# Relays.net
KiCad netlist of a schematic drawn in Altium Designer
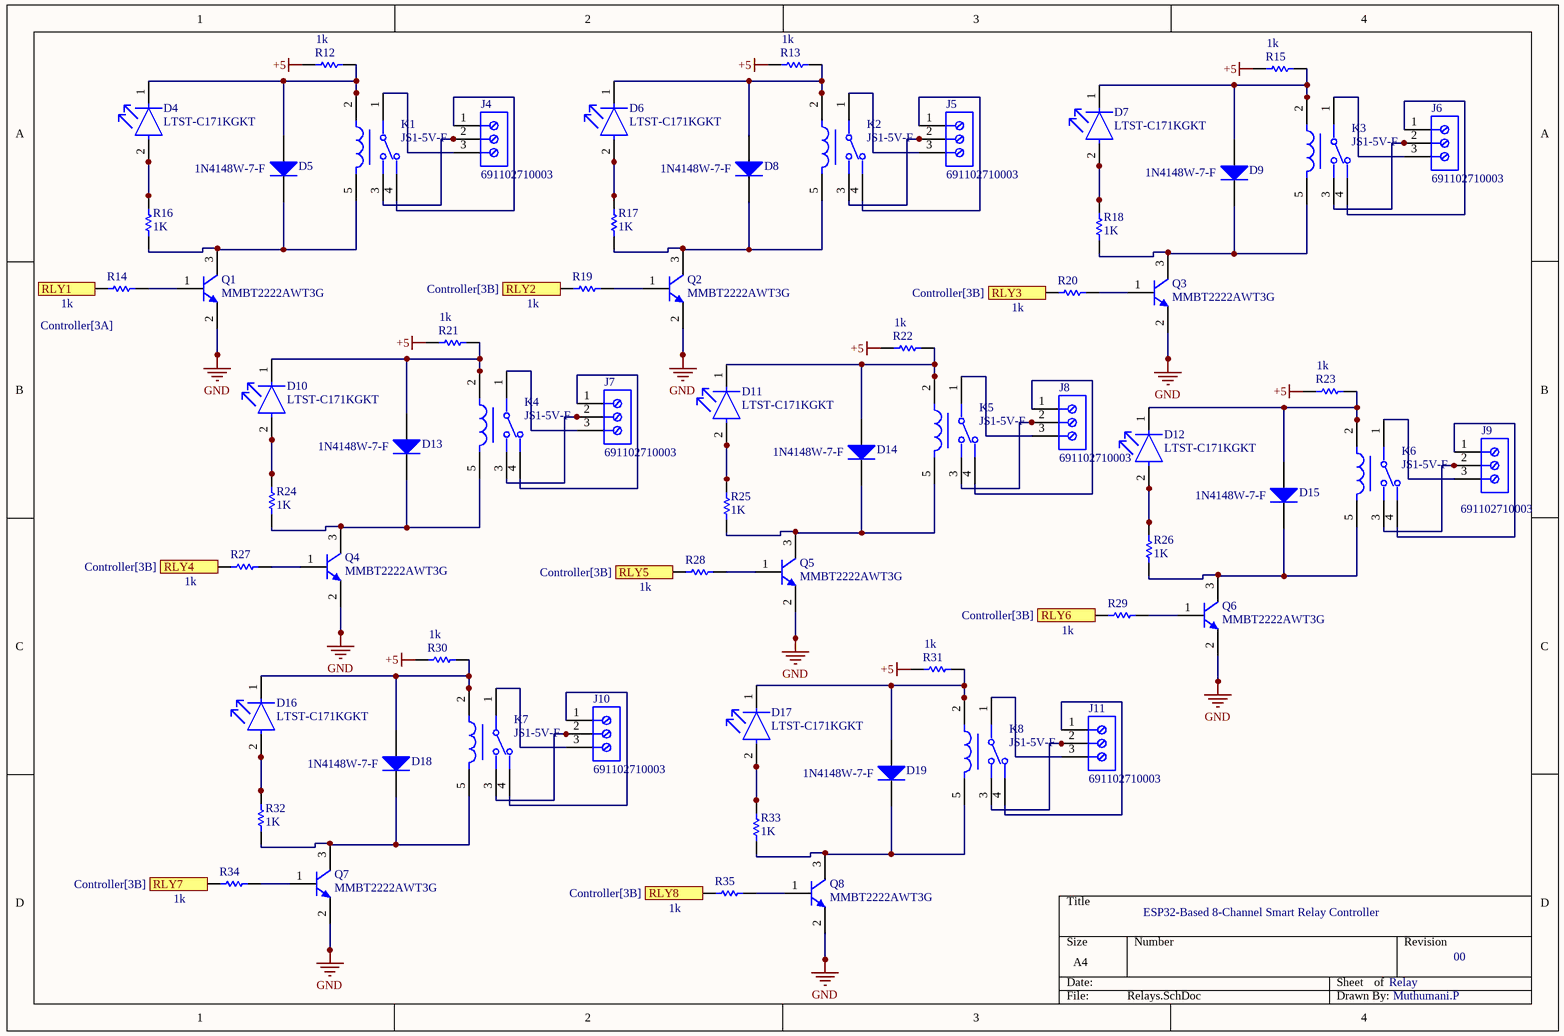
[diagram p0: Relays.SchDoc]

(export (version "E")
  (design (tool "Eeschema 10.0.6"))
  (components
    (comp (ref "D4")
      (value "LTST-C171KGKT")
      (footprint "FP-LTST-C171KGKT-MFG")
      (description "LED GREEN CLEAR SMD")
      (libsource (lib "Altium Content Vault") (part "8706943c75ba83719d021d2fdc84c58"))
    )
    (comp (ref "D5")
      (value "1N4148W-7-F")
      (footprint "DIOD-SOD123-2_V")
      (description "Fast Switching Diode, 100 V, 0.15 A, -65 to 150 degC, 2-Pin?SOD123, RoHS, Tape and Reel")
      (fields (field (name "MANUFACTURER") "DiodesIncorporated"))
      (libsource (lib "Altium Content Vault") (part "D-AK-2"))
    )
    (comp (ref "D6")
      (value "LTST-C171KGKT")
      (footprint "FP-LTST-C171KGKT-MFG")
      (description "LED GREEN CLEAR SMD")
      (libsource (lib "Altium Content Vault") (part "8706943c75ba83719d021d2fdc84c58"))
    )
    (comp (ref "D7")
      (value "LTST-C171KGKT")
      (footprint "FP-LTST-C171KGKT-MFG")
      (description "LED GREEN CLEAR SMD")
      (libsource (lib "Altium Content Vault") (part "8706943c75ba83719d021d2fdc84c58"))
    )
    (comp (ref "D8")
      (value "1N4148W-7-F")
      (footprint "DIOD-SOD123-2_V")
      (description "Fast Switching Diode, 100 V, 0.15 A, -65 to 150 degC, 2-Pin?SOD123, RoHS, Tape and Reel")
      (fields (field (name "MANUFACTURER") "DiodesIncorporated"))
      (libsource (lib "Altium Content Vault") (part "D-AK-2"))
    )
    (comp (ref "D9")
      (value "1N4148W-7-F")
      (footprint "DIOD-SOD123-2_V")
      (description "Fast Switching Diode, 100 V, 0.15 A, -65 to 150 degC, 2-Pin?SOD123, RoHS, Tape and Reel")
      (fields (field (name "MANUFACTURER") "DiodesIncorporated"))
      (libsource (lib "Altium Content Vault") (part "D-AK-2"))
    )
    (comp (ref "D10")
      (value "LTST-C171KGKT")
      (footprint "FP-LTST-C171KGKT-MFG")
      (description "LED GREEN CLEAR SMD")
      (libsource (lib "Altium Content Vault") (part "8706943c75ba83719d021d2fdc84c58"))
    )
    (comp (ref "D11")
      (value "LTST-C171KGKT")
      (footprint "FP-LTST-C171KGKT-MFG")
      (description "LED GREEN CLEAR SMD")
      (libsource (lib "Altium Content Vault") (part "8706943c75ba83719d021d2fdc84c58"))
    )
    (comp (ref "D12")
      (value "LTST-C171KGKT")
      (footprint "FP-LTST-C171KGKT-MFG")
      (description "LED GREEN CLEAR SMD")
      (libsource (lib "Altium Content Vault") (part "8706943c75ba83719d021d2fdc84c58"))
    )
    (comp (ref "D13")
      (value "1N4148W-7-F")
      (footprint "DIOD-SOD123-2_V")
      (description "Fast Switching Diode, 100 V, 0.15 A, -65 to 150 degC, 2-Pin?SOD123, RoHS, Tape and Reel")
      (fields (field (name "MANUFACTURER") "DiodesIncorporated"))
      (libsource (lib "Altium Content Vault") (part "D-AK-2"))
    )
    (comp (ref "D14")
      (value "1N4148W-7-F")
      (footprint "DIOD-SOD123-2_V")
      (description "Fast Switching Diode, 100 V, 0.15 A, -65 to 150 degC, 2-Pin?SOD123, RoHS, Tape and Reel")
      (fields (field (name "MANUFACTURER") "DiodesIncorporated"))
      (libsource (lib "Altium Content Vault") (part "D-AK-2"))
    )
    (comp (ref "D15")
      (value "1N4148W-7-F")
      (footprint "DIOD-SOD123-2_V")
      (description "Fast Switching Diode, 100 V, 0.15 A, -65 to 150 degC, 2-Pin?SOD123, RoHS, Tape and Reel")
      (fields (field (name "MANUFACTURER") "DiodesIncorporated"))
      (libsource (lib "Altium Content Vault") (part "D-AK-2"))
    )
    (comp (ref "D16")
      (value "LTST-C171KGKT")
      (footprint "FP-LTST-C171KGKT-MFG")
      (description "LED GREEN CLEAR SMD")
      (libsource (lib "Altium Content Vault") (part "8706943c75ba83719d021d2fdc84c58"))
    )
    (comp (ref "D17")
      (value "LTST-C171KGKT")
      (footprint "FP-LTST-C171KGKT-MFG")
      (description "LED GREEN CLEAR SMD")
      (libsource (lib "Altium Content Vault") (part "8706943c75ba83719d021d2fdc84c58"))
    )
    (comp (ref "D18")
      (value "1N4148W-7-F")
      (footprint "DIOD-SOD123-2_V")
      (description "Fast Switching Diode, 100 V, 0.15 A, -65 to 150 degC, 2-Pin?SOD123, RoHS, Tape and Reel")
      (fields (field (name "MANUFACTURER") "DiodesIncorporated"))
      (libsource (lib "Altium Content Vault") (part "D-AK-2"))
    )
    (comp (ref "D19")
      (value "1N4148W-7-F")
      (footprint "DIOD-SOD123-2_V")
      (description "Fast Switching Diode, 100 V, 0.15 A, -65 to 150 degC, 2-Pin?SOD123, RoHS, Tape and Reel")
      (fields (field (name "MANUFACTURER") "DiodesIncorporated"))
      (libsource (lib "Altium Content Vault") (part "D-AK-2"))
    )
    (comp (ref "J4")
      (value "691102710003")
      (footprint "691102710003")
      (description "102 Series 5MM Pitch Straight, Pcb Terminal Block, Through Hole, 3 Way")
      (fields (field (name "VOLTAGE") "300V"))
      (libsource (lib "Altium Content Vault") (part "TBL - 1R - 03P - Screw"))
    )
    (comp (ref "J5")
      (value "691102710003")
      (footprint "691102710003")
      (description "102 Series 5MM Pitch Straight, Pcb Terminal Block, Through Hole, 3 Way")
      (fields (field (name "VOLTAGE") "300V"))
      (libsource (lib "Altium Content Vault") (part "TBL - 1R - 03P - Screw"))
    )
    (comp (ref "J6")
      (value "691102710003")
      (footprint "691102710003")
      (description "102 Series 5MM Pitch Straight, Pcb Terminal Block, Through Hole, 3 Way")
      (fields (field (name "VOLTAGE") "300V"))
      (libsource (lib "Altium Content Vault") (part "TBL - 1R - 03P - Screw"))
    )
    (comp (ref "J7")
      (value "691102710003")
      (footprint "691102710003")
      (description "102 Series 5MM Pitch Straight, Pcb Terminal Block, Through Hole, 3 Way")
      (fields (field (name "VOLTAGE") "300V"))
      (libsource (lib "Altium Content Vault") (part "TBL - 1R - 03P - Screw"))
    )
    (comp (ref "J8")
      (value "691102710003")
      (footprint "691102710003")
      (description "102 Series 5MM Pitch Straight, Pcb Terminal Block, Through Hole, 3 Way")
      (fields (field (name "VOLTAGE") "300V"))
      (libsource (lib "Altium Content Vault") (part "TBL - 1R - 03P - Screw"))
    )
    (comp (ref "J9")
      (value "691102710003")
      (footprint "691102710003")
      (description "102 Series 5MM Pitch Straight, Pcb Terminal Block, Through Hole, 3 Way")
      (fields (field (name "VOLTAGE") "300V"))
      (libsource (lib "Altium Content Vault") (part "TBL - 1R - 03P - Screw"))
    )
    (comp (ref "J10")
      (value "691102710003")
      (footprint "691102710003")
      (description "102 Series 5MM Pitch Straight, Pcb Terminal Block, Through Hole, 3 Way")
      (fields (field (name "VOLTAGE") "300V"))
      (libsource (lib "Altium Content Vault") (part "TBL - 1R - 03P - Screw"))
    )
    (comp (ref "J11")
      (value "691102710003")
      (footprint "691102710003")
      (description "102 Series 5MM Pitch Straight, Pcb Terminal Block, Through Hole, 3 Way")
      (fields (field (name "VOLTAGE") "300V"))
      (libsource (lib "Altium Content Vault") (part "TBL - 1R - 03P - Screw"))
    )
    (comp (ref "K1")
      (value "JS1-5V-F")
      (footprint "FP-JS1-5V-F-MFG")
      (description "RELAY GEN PURPOSE SPDT 10A 5V")
      (fields
        (field (name "OCTOPART") "https://octopart.com/js1-5v-f-panasonic-39428621")
        (field (name "MANUFACTURER") "Panasonic")
      )
      (libsource (lib "Altium Content Vault") (part "250623531296f86beaf95f2bc4a6d4c"))
    )
    (comp (ref "K2")
      (value "JS1-5V-F")
      (footprint "FP-JS1-5V-F-MFG")
      (description "RELAY GEN PURPOSE SPDT 10A 5V")
      (fields
        (field (name "OCTOPART") "https://octopart.com/js1-5v-f-panasonic-39428621")
        (field (name "MANUFACTURER") "Panasonic")
      )
      (libsource (lib "Altium Content Vault") (part "250623531296f86beaf95f2bc4a6d4c"))
    )
    (comp (ref "K3")
      (value "JS1-5V-F")
      (footprint "FP-JS1-5V-F-MFG")
      (description "RELAY GEN PURPOSE SPDT 10A 5V")
      (fields
        (field (name "OCTOPART") "https://octopart.com/js1-5v-f-panasonic-39428621")
        (field (name "MANUFACTURER") "Panasonic")
      )
      (libsource (lib "Altium Content Vault") (part "250623531296f86beaf95f2bc4a6d4c"))
    )
    (comp (ref "K4")
      (value "JS1-5V-F")
      (footprint "FP-JS1-5V-F-MFG")
      (description "RELAY GEN PURPOSE SPDT 10A 5V")
      (fields
        (field (name "OCTOPART") "https://octopart.com/js1-5v-f-panasonic-39428621")
        (field (name "MANUFACTURER") "Panasonic")
      )
      (libsource (lib "Altium Content Vault") (part "250623531296f86beaf95f2bc4a6d4c"))
    )
    (comp (ref "K5")
      (value "JS1-5V-F")
      (footprint "FP-JS1-5V-F-MFG")
      (description "RELAY GEN PURPOSE SPDT 10A 5V")
      (fields
        (field (name "OCTOPART") "https://octopart.com/js1-5v-f-panasonic-39428621")
        (field (name "MANUFACTURER") "Panasonic")
      )
      (libsource (lib "Altium Content Vault") (part "250623531296f86beaf95f2bc4a6d4c"))
    )
    (comp (ref "K6")
      (value "JS1-5V-F")
      (footprint "FP-JS1-5V-F-MFG")
      (description "RELAY GEN PURPOSE SPDT 10A 5V")
      (fields
        (field (name "OCTOPART") "https://octopart.com/js1-5v-f-panasonic-39428621")
        (field (name "MANUFACTURER") "Panasonic")
      )
      (libsource (lib "Altium Content Vault") (part "250623531296f86beaf95f2bc4a6d4c"))
    )
    (comp (ref "K7")
      (value "JS1-5V-F")
      (footprint "FP-JS1-5V-F-MFG")
      (description "RELAY GEN PURPOSE SPDT 10A 5V")
      (fields
        (field (name "OCTOPART") "https://octopart.com/js1-5v-f-panasonic-39428621")
        (field (name "MANUFACTURER") "Panasonic")
      )
      (libsource (lib "Altium Content Vault") (part "250623531296f86beaf95f2bc4a6d4c"))
    )
    (comp (ref "K8")
      (value "JS1-5V-F")
      (footprint "FP-JS1-5V-F-MFG")
      (description "RELAY GEN PURPOSE SPDT 10A 5V")
      (fields
        (field (name "OCTOPART") "https://octopart.com/js1-5v-f-panasonic-39428621")
        (field (name "MANUFACTURER") "Panasonic")
      )
      (libsource (lib "Altium Content Vault") (part "250623531296f86beaf95f2bc4a6d4c"))
    )
    (comp (ref "Q1")
      (value "MMBT2222AWT3G")
      (footprint "ONSC-SC-70-3-419-04_V")
      (description "General Purpose Transistor, NPN Silicon, 3-Pin SC70, Pb-Free, Tape and Reel")
      (fields (field (name "MANUFACTURER") "On Semiconductor"))
      (libsource (lib "Altium Content Vault") (part "ONSC-NPN-B1E2C3-3"))
    )
    (comp (ref "Q2")
      (value "MMBT2222AWT3G")
      (footprint "ONSC-SC-70-3-419-04_V")
      (description "General Purpose Transistor, NPN Silicon, 3-Pin SC70, Pb-Free, Tape and Reel")
      (fields (field (name "MANUFACTURER") "On Semiconductor"))
      (libsource (lib "Altium Content Vault") (part "ONSC-NPN-B1E2C3-3"))
    )
    (comp (ref "Q3")
      (value "MMBT2222AWT3G")
      (footprint "ONSC-SC-70-3-419-04_V")
      (description "General Purpose Transistor, NPN Silicon, 3-Pin SC70, Pb-Free, Tape and Reel")
      (fields (field (name "MANUFACTURER") "On Semiconductor"))
      (libsource (lib "Altium Content Vault") (part "ONSC-NPN-B1E2C3-3"))
    )
    (comp (ref "Q4")
      (value "MMBT2222AWT3G")
      (footprint "ONSC-SC-70-3-419-04_V")
      (description "General Purpose Transistor, NPN Silicon, 3-Pin SC70, Pb-Free, Tape and Reel")
      (fields (field (name "MANUFACTURER") "On Semiconductor"))
      (libsource (lib "Altium Content Vault") (part "ONSC-NPN-B1E2C3-3"))
    )
    (comp (ref "Q5")
      (value "MMBT2222AWT3G")
      (footprint "ONSC-SC-70-3-419-04_V")
      (description "General Purpose Transistor, NPN Silicon, 3-Pin SC70, Pb-Free, Tape and Reel")
      (fields (field (name "MANUFACTURER") "On Semiconductor"))
      (libsource (lib "Altium Content Vault") (part "ONSC-NPN-B1E2C3-3"))
    )
    (comp (ref "Q6")
      (value "MMBT2222AWT3G")
      (footprint "ONSC-SC-70-3-419-04_V")
      (description "General Purpose Transistor, NPN Silicon, 3-Pin SC70, Pb-Free, Tape and Reel")
      (fields (field (name "MANUFACTURER") "On Semiconductor"))
      (libsource (lib "Altium Content Vault") (part "ONSC-NPN-B1E2C3-3"))
    )
    (comp (ref "Q7")
      (value "MMBT2222AWT3G")
      (footprint "ONSC-SC-70-3-419-04_V")
      (description "General Purpose Transistor, NPN Silicon, 3-Pin SC70, Pb-Free, Tape and Reel")
      (fields (field (name "MANUFACTURER") "On Semiconductor"))
      (libsource (lib "Altium Content Vault") (part "ONSC-NPN-B1E2C3-3"))
    )
    (comp (ref "Q8")
      (value "MMBT2222AWT3G")
      (footprint "ONSC-SC-70-3-419-04_V")
      (description "General Purpose Transistor, NPN Silicon, 3-Pin SC70, Pb-Free, Tape and Reel")
      (fields (field (name "MANUFACTURER") "On Semiconductor"))
      (libsource (lib "Altium Content Vault") (part "ONSC-NPN-B1E2C3-3"))
    )
    (comp (ref "R12")
      (value "1k")
      (footprint "RESC2013X60X35ML10T20")
      (description "Chip Resistor, 1 KOhm, +/- 1%, 125 mW, -55 to 155 degC, 0805 (2012 Metric), RoHS, Tape and Reel")
      (fields (field (name "TOLERANCE") "1%") (field (name "MANUFACTURER") "Yageo"))
      (libsource (lib "Altium Content Vault") (part "RES-2"))
    )
    (comp (ref "R13")
      (value "1k")
      (footprint "RESC2013X60X35ML10T20")
      (description "Chip Resistor, 1 KOhm, +/- 1%, 125 mW, -55 to 155 degC, 0805 (2012 Metric), RoHS, Tape and Reel")
      (fields (field (name "TOLERANCE") "1%") (field (name "MANUFACTURER") "Yageo"))
      (libsource (lib "Altium Content Vault") (part "RES-2"))
    )
    (comp (ref "R14")
      (value "1k")
      (footprint "RESC2013X60X35ML10T20")
      (description "Chip Resistor, 1 KOhm, +/- 1%, 125 mW, -55 to 155 degC, 0805 (2012 Metric), RoHS, Tape and Reel")
      (fields (field (name "TOLERANCE") "1%") (field (name "MANUFACTURER") "Yageo"))
      (libsource (lib "Altium Content Vault") (part "RES-2"))
    )
    (comp (ref "R15")
      (value "1k")
      (footprint "RESC2013X60X35ML10T20")
      (description "Chip Resistor, 1 KOhm, +/- 1%, 125 mW, -55 to 155 degC, 0805 (2012 Metric), RoHS, Tape and Reel")
      (fields (field (name "TOLERANCE") "1%") (field (name "MANUFACTURER") "Yageo"))
      (libsource (lib "Altium Content Vault") (part "RES-2"))
    )
    (comp (ref "R16")
      (value "1K")
      (footprint "RESC2013X60X35ML10T20")
      (description "Chip Resistor, 1 KOhm, +/- 1%, 125 mW, -55 to 155 degC, 0805 (2012 Metric), RoHS, Tape and Reel")
      (fields (field (name "TOLERANCE") "1%") (field (name "MANUFACTURER") "Yageo"))
      (libsource (lib "Altium Content Vault") (part "RES-2"))
    )
    (comp (ref "R17")
      (value "1K")
      (footprint "RESC2013X60X35ML10T20")
      (description "Chip Resistor, 1 KOhm, +/- 1%, 125 mW, -55 to 155 degC, 0805 (2012 Metric), RoHS, Tape and Reel")
      (fields (field (name "TOLERANCE") "1%") (field (name "MANUFACTURER") "Yageo"))
      (libsource (lib "Altium Content Vault") (part "RES-2"))
    )
    (comp (ref "R18")
      (value "1K")
      (footprint "RESC2013X60X35ML10T20")
      (description "Chip Resistor, 1 KOhm, +/- 1%, 125 mW, -55 to 155 degC, 0805 (2012 Metric), RoHS, Tape and Reel")
      (fields (field (name "TOLERANCE") "1%") (field (name "MANUFACTURER") "Yageo"))
      (libsource (lib "Altium Content Vault") (part "RES-2"))
    )
    (comp (ref "R19")
      (value "1k")
      (footprint "RESC2013X60X35ML10T20")
      (description "Chip Resistor, 1 KOhm, +/- 1%, 125 mW, -55 to 155 degC, 0805 (2012 Metric), RoHS, Tape and Reel")
      (fields (field (name "TOLERANCE") "1%") (field (name "MANUFACTURER") "Yageo"))
      (libsource (lib "Altium Content Vault") (part "RES-2"))
    )
    (comp (ref "R20")
      (value "1k")
      (footprint "RESC2013X60X35ML10T20")
      (description "Chip Resistor, 1 KOhm, +/- 1%, 125 mW, -55 to 155 degC, 0805 (2012 Metric), RoHS, Tape and Reel")
      (fields (field (name "TOLERANCE") "1%") (field (name "MANUFACTURER") "Yageo"))
      (libsource (lib "Altium Content Vault") (part "RES-2"))
    )
    (comp (ref "R21")
      (value "1k")
      (footprint "RESC2013X60X35ML10T20")
      (description "Chip Resistor, 1 KOhm, +/- 1%, 125 mW, -55 to 155 degC, 0805 (2012 Metric), RoHS, Tape and Reel")
      (fields (field (name "TOLERANCE") "1%") (field (name "MANUFACTURER") "Yageo"))
      (libsource (lib "Altium Content Vault") (part "RES-2"))
    )
    (comp (ref "R22")
      (value "1k")
      (footprint "RESC2013X60X35ML10T20")
      (description "Chip Resistor, 1 KOhm, +/- 1%, 125 mW, -55 to 155 degC, 0805 (2012 Metric), RoHS, Tape and Reel")
      (fields (field (name "TOLERANCE") "1%") (field (name "MANUFACTURER") "Yageo"))
      (libsource (lib "Altium Content Vault") (part "RES-2"))
    )
    (comp (ref "R23")
      (value "1k")
      (footprint "RESC2013X60X35ML10T20")
      (description "Chip Resistor, 1 KOhm, +/- 1%, 125 mW, -55 to 155 degC, 0805 (2012 Metric), RoHS, Tape and Reel")
      (fields (field (name "TOLERANCE") "1%") (field (name "MANUFACTURER") "Yageo"))
      (libsource (lib "Altium Content Vault") (part "RES-2"))
    )
    (comp (ref "R24")
      (value "1K")
      (footprint "RESC2013X60X35ML10T20")
      (description "Chip Resistor, 1 KOhm, +/- 1%, 125 mW, -55 to 155 degC, 0805 (2012 Metric), RoHS, Tape and Reel")
      (fields (field (name "TOLERANCE") "1%") (field (name "MANUFACTURER") "Yageo"))
      (libsource (lib "Altium Content Vault") (part "RES-2"))
    )
    (comp (ref "R25")
      (value "1K")
      (footprint "RESC2013X60X35ML10T20")
      (description "Chip Resistor, 1 KOhm, +/- 1%, 125 mW, -55 to 155 degC, 0805 (2012 Metric), RoHS, Tape and Reel")
      (fields (field (name "TOLERANCE") "1%") (field (name "MANUFACTURER") "Yageo"))
      (libsource (lib "Altium Content Vault") (part "RES-2"))
    )
    (comp (ref "R26")
      (value "1K")
      (footprint "RESC2013X60X35ML10T20")
      (description "Chip Resistor, 1 KOhm, +/- 1%, 125 mW, -55 to 155 degC, 0805 (2012 Metric), RoHS, Tape and Reel")
      (fields (field (name "TOLERANCE") "1%") (field (name "MANUFACTURER") "Yageo"))
      (libsource (lib "Altium Content Vault") (part "RES-2"))
    )
    (comp (ref "R27")
      (value "1k")
      (footprint "RESC2013X60X35ML10T20")
      (description "Chip Resistor, 1 KOhm, +/- 1%, 125 mW, -55 to 155 degC, 0805 (2012 Metric), RoHS, Tape and Reel")
      (fields (field (name "TOLERANCE") "1%") (field (name "MANUFACTURER") "Yageo"))
      (libsource (lib "Altium Content Vault") (part "RES-2"))
    )
    (comp (ref "R28")
      (value "1k")
      (footprint "RESC2013X60X35ML10T20")
      (description "Chip Resistor, 1 KOhm, +/- 1%, 125 mW, -55 to 155 degC, 0805 (2012 Metric), RoHS, Tape and Reel")
      (fields (field (name "TOLERANCE") "1%") (field (name "MANUFACTURER") "Yageo"))
      (libsource (lib "Altium Content Vault") (part "RES-2"))
    )
    (comp (ref "R29")
      (value "1k")
      (footprint "RESC2013X60X35ML10T20")
      (description "Chip Resistor, 1 KOhm, +/- 1%, 125 mW, -55 to 155 degC, 0805 (2012 Metric), RoHS, Tape and Reel")
      (fields (field (name "TOLERANCE") "1%") (field (name "MANUFACTURER") "Yageo"))
      (libsource (lib "Altium Content Vault") (part "RES-2"))
    )
    (comp (ref "R30")
      (value "1k")
      (footprint "RESC2013X60X35ML10T20")
      (description "Chip Resistor, 1 KOhm, +/- 1%, 125 mW, -55 to 155 degC, 0805 (2012 Metric), RoHS, Tape and Reel")
      (fields (field (name "TOLERANCE") "1%") (field (name "MANUFACTURER") "Yageo"))
      (libsource (lib "Altium Content Vault") (part "RES-2"))
    )
    (comp (ref "R31")
      (value "1k")
      (footprint "RESC2013X60X35ML10T20")
      (description "Chip Resistor, 1 KOhm, +/- 1%, 125 mW, -55 to 155 degC, 0805 (2012 Metric), RoHS, Tape and Reel")
      (fields (field (name "TOLERANCE") "1%") (field (name "MANUFACTURER") "Yageo"))
      (libsource (lib "Altium Content Vault") (part "RES-2"))
    )
    (comp (ref "R32")
      (value "1K")
      (footprint "RESC2013X60X35ML10T20")
      (description "Chip Resistor, 1 KOhm, +/- 1%, 125 mW, -55 to 155 degC, 0805 (2012 Metric), RoHS, Tape and Reel")
      (fields (field (name "TOLERANCE") "1%") (field (name "MANUFACTURER") "Yageo"))
      (libsource (lib "Altium Content Vault") (part "RES-2"))
    )
    (comp (ref "R33")
      (value "1K")
      (footprint "RESC2013X60X35ML10T20")
      (description "Chip Resistor, 1 KOhm, +/- 1%, 125 mW, -55 to 155 degC, 0805 (2012 Metric), RoHS, Tape and Reel")
      (fields (field (name "TOLERANCE") "1%") (field (name "MANUFACTURER") "Yageo"))
      (libsource (lib "Altium Content Vault") (part "RES-2"))
    )
    (comp (ref "R34")
      (value "1k")
      (footprint "RESC2013X60X35ML10T20")
      (description "Chip Resistor, 1 KOhm, +/- 1%, 125 mW, -55 to 155 degC, 0805 (2012 Metric), RoHS, Tape and Reel")
      (fields (field (name "TOLERANCE") "1%") (field (name "MANUFACTURER") "Yageo"))
      (libsource (lib "Altium Content Vault") (part "RES-2"))
    )
    (comp (ref "R35")
      (value "1k")
      (footprint "RESC2013X60X35ML10T20")
      (description "Chip Resistor, 1 KOhm, +/- 1%, 125 mW, -55 to 155 degC, 0805 (2012 Metric), RoHS, Tape and Reel")
      (fields (field (name "TOLERANCE") "1%") (field (name "MANUFACTURER") "Yageo"))
      (libsource (lib "Altium Content Vault") (part "RES-2"))
    )
  )
  (nets
    (net (code "1") (name "+5") (class "Default")
      (node (ref "R12") (pin "2") (pinfunction "2_2") (pintype "passive"))
      (node (ref "R13") (pin "2") (pinfunction "2_2") (pintype "passive"))
      (node (ref "R15") (pin "2") (pinfunction "2_2") (pintype "passive"))
      (node (ref "R21") (pin "2") (pinfunction "2_2") (pintype "passive"))
      (node (ref "R22") (pin "2") (pinfunction "2_2") (pintype "passive"))
      (node (ref "R23") (pin "2") (pinfunction "2_2") (pintype "passive"))
      (node (ref "R30") (pin "2") (pinfunction "2_2") (pintype "passive"))
      (node (ref "R31") (pin "2") (pinfunction "2_2") (pintype "passive"))
    )
    (net (code "2") (name "/RLY1") (class "Default")
      (node (ref "R14") (pin "1") (pinfunction "1_1") (pintype "passive"))
    )
    (net (code "3") (name "/RLY2") (class "Default")
      (node (ref "R19") (pin "1") (pinfunction "1_1") (pintype "passive"))
    )
    (net (code "4") (name "/RLY3") (class "Default")
      (node (ref "R20") (pin "1") (pinfunction "1_1") (pintype "passive"))
    )
    (net (code "5") (name "/RLY4") (class "Default")
      (node (ref "R27") (pin "1") (pinfunction "1_1") (pintype "passive"))
    )
    (net (code "6") (name "/RLY5") (class "Default")
      (node (ref "R28") (pin "1") (pinfunction "1_1") (pintype "passive"))
    )
    (net (code "7") (name "/RLY6") (class "Default")
      (node (ref "R29") (pin "1") (pinfunction "1_1") (pintype "passive"))
    )
    (net (code "8") (name "/RLY7") (class "Default")
      (node (ref "R34") (pin "1") (pinfunction "1_1") (pintype "passive"))
    )
    (net (code "9") (name "/RLY8") (class "Default")
      (node (ref "R35") (pin "1") (pinfunction "1_1") (pintype "passive"))
    )
    (net (code "10") (name "GND") (class "Default")
      (node (ref "Q1") (pin "2") (pinfunction "E_2") (pintype "passive"))
      (node (ref "Q2") (pin "2") (pinfunction "E_2") (pintype "passive"))
      (node (ref "Q3") (pin "2") (pinfunction "E_2") (pintype "passive"))
      (node (ref "Q4") (pin "2") (pinfunction "E_2") (pintype "passive"))
      (node (ref "Q5") (pin "2") (pinfunction "E_2") (pintype "passive"))
      (node (ref "Q6") (pin "2") (pinfunction "E_2") (pintype "passive"))
      (node (ref "Q7") (pin "2") (pinfunction "E_2") (pintype "passive"))
      (node (ref "Q8") (pin "2") (pinfunction "E_2") (pintype "passive"))
    )
    (net (code "11") (name "Net-(D4-A)") (class "Default")
      (node (ref "D4") (pin "2") (pinfunction "A_2") (pintype "passive"))
      (node (ref "R16") (pin "2") (pinfunction "2_2") (pintype "passive"))
    )
    (net (code "12") (name "Net-(D4-C)") (class "Default")
      (node (ref "D4") (pin "1") (pinfunction "C_1") (pintype "passive"))
      (node (ref "D5") (pin "1") (pinfunction "A_1") (pintype "passive"))
      (node (ref "K1") (pin "2") (pinfunction "1_COIL_2") (pintype "passive"))
      (node (ref "R12") (pin "1") (pinfunction "1_1") (pintype "passive"))
    )
    (net (code "13") (name "Net-(D5-K)") (class "Default")
      (node (ref "D5") (pin "2") (pinfunction "K_2") (pintype "passive"))
      (node (ref "K1") (pin "5") (pinfunction "2_COIL_5") (pintype "passive"))
      (node (ref "Q1") (pin "3") (pinfunction "C_3") (pintype "passive"))
      (node (ref "R16") (pin "1") (pinfunction "1_1") (pintype "passive"))
    )
    (net (code "14") (name "Net-(D6-A)") (class "Default")
      (node (ref "D6") (pin "2") (pinfunction "A_2") (pintype "passive"))
      (node (ref "R17") (pin "2") (pinfunction "2_2") (pintype "passive"))
    )
    (net (code "15") (name "Net-(D6-C)") (class "Default")
      (node (ref "D6") (pin "1") (pinfunction "C_1") (pintype "passive"))
      (node (ref "D8") (pin "1") (pinfunction "A_1") (pintype "passive"))
      (node (ref "K2") (pin "2") (pinfunction "1_COIL_2") (pintype "passive"))
      (node (ref "R13") (pin "1") (pinfunction "1_1") (pintype "passive"))
    )
    (net (code "16") (name "Net-(D7-A)") (class "Default")
      (node (ref "D7") (pin "2") (pinfunction "A_2") (pintype "passive"))
      (node (ref "R18") (pin "2") (pinfunction "2_2") (pintype "passive"))
    )
    (net (code "17") (name "Net-(D7-C)") (class "Default")
      (node (ref "D7") (pin "1") (pinfunction "C_1") (pintype "passive"))
      (node (ref "D9") (pin "1") (pinfunction "A_1") (pintype "passive"))
      (node (ref "K3") (pin "2") (pinfunction "1_COIL_2") (pintype "passive"))
      (node (ref "R15") (pin "1") (pinfunction "1_1") (pintype "passive"))
    )
    (net (code "18") (name "Net-(D8-K)") (class "Default")
      (node (ref "D8") (pin "2") (pinfunction "K_2") (pintype "passive"))
      (node (ref "K2") (pin "5") (pinfunction "2_COIL_5") (pintype "passive"))
      (node (ref "Q2") (pin "3") (pinfunction "C_3") (pintype "passive"))
      (node (ref "R17") (pin "1") (pinfunction "1_1") (pintype "passive"))
    )
    (net (code "19") (name "Net-(D9-K)") (class "Default")
      (node (ref "D9") (pin "2") (pinfunction "K_2") (pintype "passive"))
      (node (ref "K3") (pin "5") (pinfunction "2_COIL_5") (pintype "passive"))
      (node (ref "Q3") (pin "3") (pinfunction "C_3") (pintype "passive"))
      (node (ref "R18") (pin "1") (pinfunction "1_1") (pintype "passive"))
    )
    (net (code "20") (name "Net-(D10-A)") (class "Default")
      (node (ref "D10") (pin "2") (pinfunction "A_2") (pintype "passive"))
      (node (ref "R24") (pin "2") (pinfunction "2_2") (pintype "passive"))
    )
    (net (code "21") (name "Net-(D10-C)") (class "Default")
      (node (ref "D10") (pin "1") (pinfunction "C_1") (pintype "passive"))
      (node (ref "D13") (pin "1") (pinfunction "A_1") (pintype "passive"))
      (node (ref "K4") (pin "2") (pinfunction "1_COIL_2") (pintype "passive"))
      (node (ref "R21") (pin "1") (pinfunction "1_1") (pintype "passive"))
    )
    (net (code "22") (name "Net-(D11-A)") (class "Default")
      (node (ref "D11") (pin "2") (pinfunction "A_2") (pintype "passive"))
      (node (ref "R25") (pin "2") (pinfunction "2_2") (pintype "passive"))
    )
    (net (code "23") (name "Net-(D11-C)") (class "Default")
      (node (ref "D11") (pin "1") (pinfunction "C_1") (pintype "passive"))
      (node (ref "D14") (pin "1") (pinfunction "A_1") (pintype "passive"))
      (node (ref "K5") (pin "2") (pinfunction "1_COIL_2") (pintype "passive"))
      (node (ref "R22") (pin "1") (pinfunction "1_1") (pintype "passive"))
    )
    (net (code "24") (name "Net-(D12-A)") (class "Default")
      (node (ref "D12") (pin "2") (pinfunction "A_2") (pintype "passive"))
      (node (ref "R26") (pin "2") (pinfunction "2_2") (pintype "passive"))
    )
    (net (code "25") (name "Net-(D12-C)") (class "Default")
      (node (ref "D12") (pin "1") (pinfunction "C_1") (pintype "passive"))
      (node (ref "D15") (pin "1") (pinfunction "A_1") (pintype "passive"))
      (node (ref "K6") (pin "2") (pinfunction "1_COIL_2") (pintype "passive"))
      (node (ref "R23") (pin "1") (pinfunction "1_1") (pintype "passive"))
    )
    (net (code "26") (name "Net-(D13-K)") (class "Default")
      (node (ref "D13") (pin "2") (pinfunction "K_2") (pintype "passive"))
      (node (ref "K4") (pin "5") (pinfunction "2_COIL_5") (pintype "passive"))
      (node (ref "Q4") (pin "3") (pinfunction "C_3") (pintype "passive"))
      (node (ref "R24") (pin "1") (pinfunction "1_1") (pintype "passive"))
    )
    (net (code "27") (name "Net-(D14-K)") (class "Default")
      (node (ref "D14") (pin "2") (pinfunction "K_2") (pintype "passive"))
      (node (ref "K5") (pin "5") (pinfunction "2_COIL_5") (pintype "passive"))
      (node (ref "Q5") (pin "3") (pinfunction "C_3") (pintype "passive"))
      (node (ref "R25") (pin "1") (pinfunction "1_1") (pintype "passive"))
    )
    (net (code "28") (name "Net-(D15-K)") (class "Default")
      (node (ref "D15") (pin "2") (pinfunction "K_2") (pintype "passive"))
      (node (ref "K6") (pin "5") (pinfunction "2_COIL_5") (pintype "passive"))
      (node (ref "Q6") (pin "3") (pinfunction "C_3") (pintype "passive"))
      (node (ref "R26") (pin "1") (pinfunction "1_1") (pintype "passive"))
    )
    (net (code "29") (name "Net-(D16-A)") (class "Default")
      (node (ref "D16") (pin "2") (pinfunction "A_2") (pintype "passive"))
      (node (ref "R32") (pin "2") (pinfunction "2_2") (pintype "passive"))
    )
    (net (code "30") (name "Net-(D16-C)") (class "Default")
      (node (ref "D16") (pin "1") (pinfunction "C_1") (pintype "passive"))
      (node (ref "D18") (pin "1") (pinfunction "A_1") (pintype "passive"))
      (node (ref "K7") (pin "2") (pinfunction "1_COIL_2") (pintype "passive"))
      (node (ref "R30") (pin "1") (pinfunction "1_1") (pintype "passive"))
    )
    (net (code "31") (name "Net-(D17-A)") (class "Default")
      (node (ref "D17") (pin "2") (pinfunction "A_2") (pintype "passive"))
      (node (ref "R33") (pin "2") (pinfunction "2_2") (pintype "passive"))
    )
    (net (code "32") (name "Net-(D17-C)") (class "Default")
      (node (ref "D17") (pin "1") (pinfunction "C_1") (pintype "passive"))
      (node (ref "D19") (pin "1") (pinfunction "A_1") (pintype "passive"))
      (node (ref "K8") (pin "2") (pinfunction "1_COIL_2") (pintype "passive"))
      (node (ref "R31") (pin "1") (pinfunction "1_1") (pintype "passive"))
    )
    (net (code "33") (name "Net-(D18-K)") (class "Default")
      (node (ref "D18") (pin "2") (pinfunction "K_2") (pintype "passive"))
      (node (ref "K7") (pin "5") (pinfunction "2_COIL_5") (pintype "passive"))
      (node (ref "Q7") (pin "3") (pinfunction "C_3") (pintype "passive"))
      (node (ref "R32") (pin "1") (pinfunction "1_1") (pintype "passive"))
    )
    (net (code "34") (name "Net-(D19-K)") (class "Default")
      (node (ref "D19") (pin "2") (pinfunction "K_2") (pintype "passive"))
      (node (ref "K8") (pin "5") (pinfunction "2_COIL_5") (pintype "passive"))
      (node (ref "Q8") (pin "3") (pinfunction "C_3") (pintype "passive"))
      (node (ref "R33") (pin "1") (pinfunction "1_1") (pintype "passive"))
    )
    (net (code "35") (name "Net-(K1-COM)") (class "Default")
      (node (ref "J4") (pin "3") (pinfunction "3_3") (pintype "passive"))
      (node (ref "K1") (pin "1") (pinfunction "COM_1") (pintype "passive"))
    )
    (net (code "36") (name "Net-(K1-N.C.)") (class "Default")
      (node (ref "J4") (pin "1") (pinfunction "1_1") (pintype "passive"))
      (node (ref "K1") (pin "4") (pinfunction "N.C._4") (pintype "passive"))
    )
    (net (code "37") (name "Net-(K1-N.O.)") (class "Default")
      (node (ref "J4") (pin "2") (pinfunction "2_2") (pintype "passive"))
      (node (ref "K1") (pin "3") (pinfunction "N.O._3") (pintype "passive"))
    )
    (net (code "38") (name "Net-(K2-COM)") (class "Default")
      (node (ref "J5") (pin "3") (pinfunction "3_3") (pintype "passive"))
      (node (ref "K2") (pin "1") (pinfunction "COM_1") (pintype "passive"))
    )
    (net (code "39") (name "Net-(K2-N.C.)") (class "Default")
      (node (ref "J5") (pin "1") (pinfunction "1_1") (pintype "passive"))
      (node (ref "K2") (pin "4") (pinfunction "N.C._4") (pintype "passive"))
    )
    (net (code "40") (name "Net-(K2-N.O.)") (class "Default")
      (node (ref "J5") (pin "2") (pinfunction "2_2") (pintype "passive"))
      (node (ref "K2") (pin "3") (pinfunction "N.O._3") (pintype "passive"))
    )
    (net (code "41") (name "Net-(K3-COM)") (class "Default")
      (node (ref "J6") (pin "3") (pinfunction "3_3") (pintype "passive"))
      (node (ref "K3") (pin "1") (pinfunction "COM_1") (pintype "passive"))
    )
    (net (code "42") (name "Net-(K3-N.C.)") (class "Default")
      (node (ref "J6") (pin "1") (pinfunction "1_1") (pintype "passive"))
      (node (ref "K3") (pin "4") (pinfunction "N.C._4") (pintype "passive"))
    )
    (net (code "43") (name "Net-(K3-N.O.)") (class "Default")
      (node (ref "J6") (pin "2") (pinfunction "2_2") (pintype "passive"))
      (node (ref "K3") (pin "3") (pinfunction "N.O._3") (pintype "passive"))
    )
    (net (code "44") (name "Net-(K4-COM)") (class "Default")
      (node (ref "J7") (pin "3") (pinfunction "3_3") (pintype "passive"))
      (node (ref "K4") (pin "1") (pinfunction "COM_1") (pintype "passive"))
    )
    (net (code "45") (name "Net-(K4-N.C.)") (class "Default")
      (node (ref "J7") (pin "1") (pinfunction "1_1") (pintype "passive"))
      (node (ref "K4") (pin "4") (pinfunction "N.C._4") (pintype "passive"))
    )
    (net (code "46") (name "Net-(K4-N.O.)") (class "Default")
      (node (ref "J7") (pin "2") (pinfunction "2_2") (pintype "passive"))
      (node (ref "K4") (pin "3") (pinfunction "N.O._3") (pintype "passive"))
    )
    (net (code "47") (name "Net-(K5-COM)") (class "Default")
      (node (ref "J8") (pin "3") (pinfunction "3_3") (pintype "passive"))
      (node (ref "K5") (pin "1") (pinfunction "COM_1") (pintype "passive"))
    )
    (net (code "48") (name "Net-(K5-N.C.)") (class "Default")
      (node (ref "J8") (pin "1") (pinfunction "1_1") (pintype "passive"))
      (node (ref "K5") (pin "4") (pinfunction "N.C._4") (pintype "passive"))
    )
    (net (code "49") (name "Net-(K5-N.O.)") (class "Default")
      (node (ref "J8") (pin "2") (pinfunction "2_2") (pintype "passive"))
      (node (ref "K5") (pin "3") (pinfunction "N.O._3") (pintype "passive"))
    )
    (net (code "50") (name "Net-(K6-COM)") (class "Default")
      (node (ref "J9") (pin "3") (pinfunction "3_3") (pintype "passive"))
      (node (ref "K6") (pin "1") (pinfunction "COM_1") (pintype "passive"))
    )
    (net (code "51") (name "Net-(K6-N.C.)") (class "Default")
      (node (ref "J9") (pin "1") (pinfunction "1_1") (pintype "passive"))
      (node (ref "K6") (pin "4") (pinfunction "N.C._4") (pintype "passive"))
    )
    (net (code "52") (name "Net-(K6-N.O.)") (class "Default")
      (node (ref "J9") (pin "2") (pinfunction "2_2") (pintype "passive"))
      (node (ref "K6") (pin "3") (pinfunction "N.O._3") (pintype "passive"))
    )
    (net (code "53") (name "Net-(K7-COM)") (class "Default")
      (node (ref "J10") (pin "3") (pinfunction "3_3") (pintype "passive"))
      (node (ref "K7") (pin "1") (pinfunction "COM_1") (pintype "passive"))
    )
    (net (code "54") (name "Net-(K7-N.C.)") (class "Default")
      (node (ref "J10") (pin "1") (pinfunction "1_1") (pintype "passive"))
      (node (ref "K7") (pin "4") (pinfunction "N.C._4") (pintype "passive"))
    )
    (net (code "55") (name "Net-(K7-N.O.)") (class "Default")
      (node (ref "J10") (pin "2") (pinfunction "2_2") (pintype "passive"))
      (node (ref "K7") (pin "3") (pinfunction "N.O._3") (pintype "passive"))
    )
    (net (code "56") (name "Net-(K8-COM)") (class "Default")
      (node (ref "J11") (pin "3") (pinfunction "3_3") (pintype "passive"))
      (node (ref "K8") (pin "1") (pinfunction "COM_1") (pintype "passive"))
    )
    (net (code "57") (name "Net-(K8-N.C.)") (class "Default")
      (node (ref "J11") (pin "1") (pinfunction "1_1") (pintype "passive"))
      (node (ref "K8") (pin "4") (pinfunction "N.C._4") (pintype "passive"))
    )
    (net (code "58") (name "Net-(K8-N.O.)") (class "Default")
      (node (ref "J11") (pin "2") (pinfunction "2_2") (pintype "passive"))
      (node (ref "K8") (pin "3") (pinfunction "N.O._3") (pintype "passive"))
    )
    (net (code "59") (name "Net-(Q1-B)") (class "Default")
      (node (ref "Q1") (pin "1") (pinfunction "B_1") (pintype "passive"))
      (node (ref "R14") (pin "2") (pinfunction "2_2") (pintype "passive"))
    )
    (net (code "60") (name "Net-(Q2-B)") (class "Default")
      (node (ref "Q2") (pin "1") (pinfunction "B_1") (pintype "passive"))
      (node (ref "R19") (pin "2") (pinfunction "2_2") (pintype "passive"))
    )
    (net (code "61") (name "Net-(Q3-B)") (class "Default")
      (node (ref "Q3") (pin "1") (pinfunction "B_1") (pintype "passive"))
      (node (ref "R20") (pin "2") (pinfunction "2_2") (pintype "passive"))
    )
    (net (code "62") (name "Net-(Q4-B)") (class "Default")
      (node (ref "Q4") (pin "1") (pinfunction "B_1") (pintype "passive"))
      (node (ref "R27") (pin "2") (pinfunction "2_2") (pintype "passive"))
    )
    (net (code "63") (name "Net-(Q5-B)") (class "Default")
      (node (ref "Q5") (pin "1") (pinfunction "B_1") (pintype "passive"))
      (node (ref "R28") (pin "2") (pinfunction "2_2") (pintype "passive"))
    )
    (net (code "64") (name "Net-(Q6-B)") (class "Default")
      (node (ref "Q6") (pin "1") (pinfunction "B_1") (pintype "passive"))
      (node (ref "R29") (pin "2") (pinfunction "2_2") (pintype "passive"))
    )
    (net (code "65") (name "Net-(Q7-B)") (class "Default")
      (node (ref "Q7") (pin "1") (pinfunction "B_1") (pintype "passive"))
      (node (ref "R34") (pin "2") (pinfunction "2_2") (pintype "passive"))
    )
    (net (code "66") (name "Net-(Q8-B)") (class "Default")
      (node (ref "Q8") (pin "1") (pinfunction "B_1") (pintype "passive"))
      (node (ref "R35") (pin "2") (pinfunction "2_2") (pintype "passive"))
    )
  )
)
